# untitled.net
KiCad netlist of a schematic drawn in EAGLE
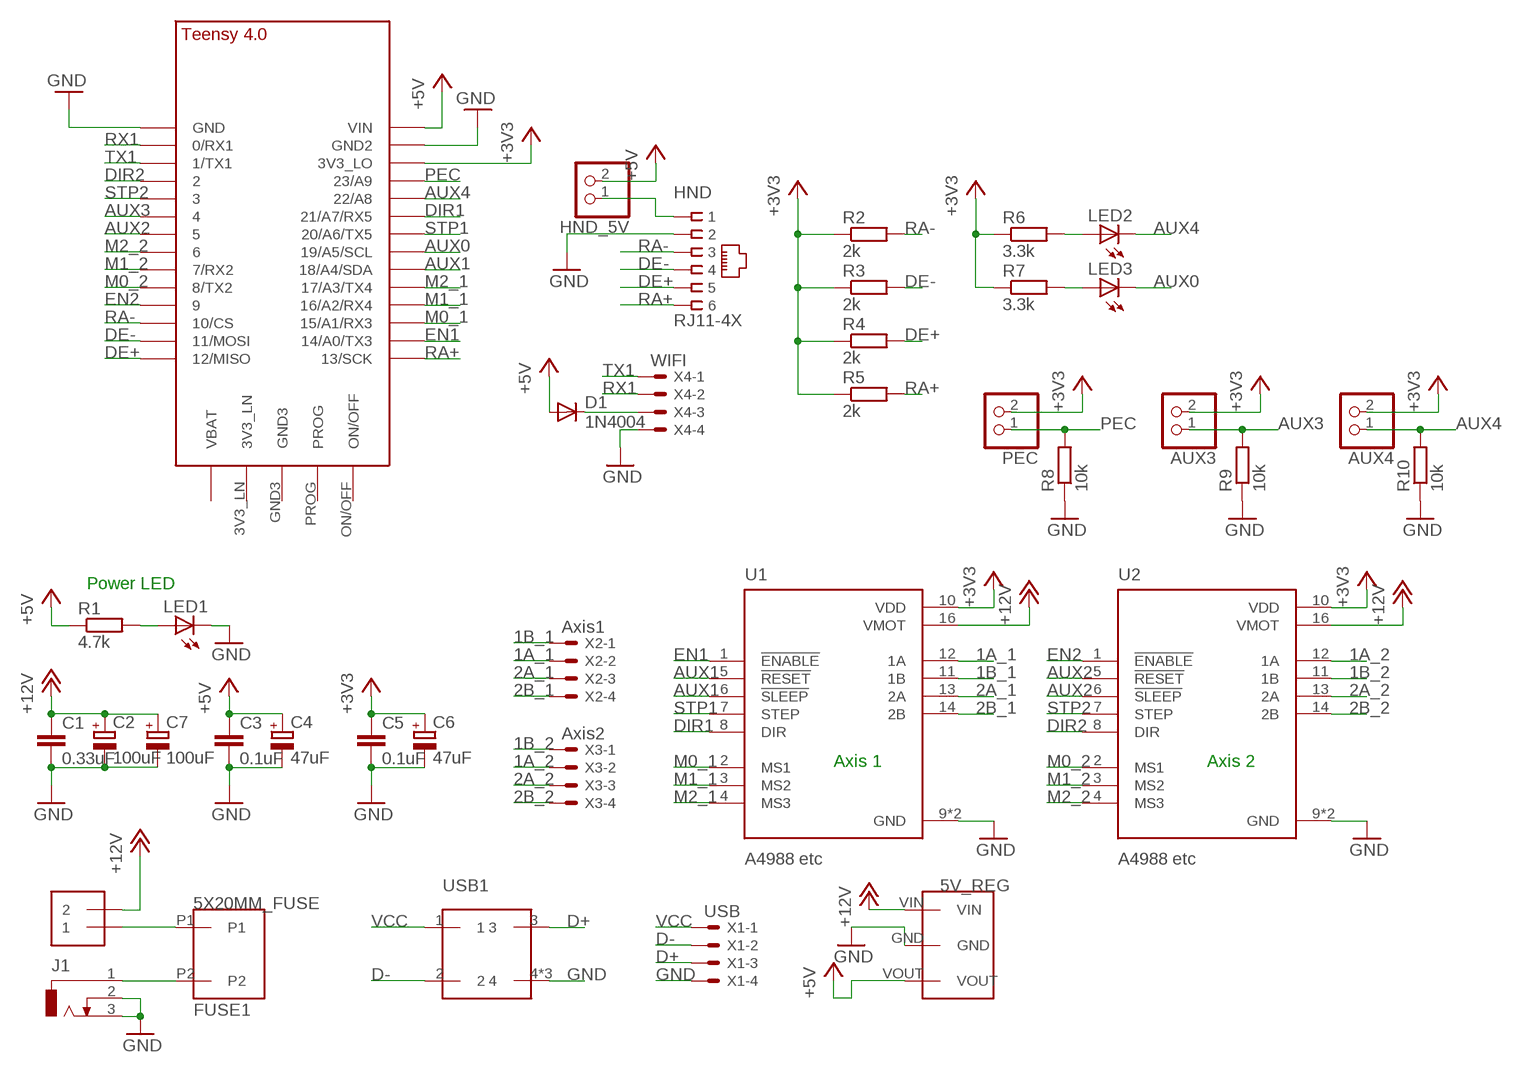
[diagram p0: schematic, sheet 1]

(export (version "E")
  (design (tool "Eeschema 10.0.6"))
  (components
    (comp (ref "5V_REG")
      (value "TSR_5V")
      (footprint "eagle-import:TSR_5V")
      (libsource (lib "eagle-import") (part "TSR_5V"))
    )
    (comp (ref "AUX3")
      (value "PINHD-1X2")
      (footprint "eagle-import:1X02")
      (libsource (lib "eagle-import") (part "PINHD-1X2"))
    )
    (comp (ref "AUX4")
      (value "PINHD-1X2")
      (footprint "eagle-import:1X02")
      (libsource (lib "eagle-import") (part "PINHD-1X2"))
    )
    (comp (ref "C1")
      (value "0.33uF")
      (footprint "eagle-import:C050-024X044")
      (libsource (lib "eagle-import") (part "C-EU050-024X044"))
    )
    (comp (ref "C2")
      (value "100uF")
      (footprint "eagle-import:E5-8,5")
      (libsource (lib "eagle-import") (part "CPOL-EUE5-8.5"))
    )
    (comp (ref "C3")
      (value "0.1uF")
      (footprint "eagle-import:C050-024X044")
      (libsource (lib "eagle-import") (part "C-EU050-024X044"))
    )
    (comp (ref "C4")
      (value "47uF")
      (footprint "eagle-import:E5-8,5")
      (libsource (lib "eagle-import") (part "CPOL-EUE5-8.5"))
    )
    (comp (ref "C5")
      (value "0.1uF")
      (footprint "eagle-import:C050-024X044")
      (libsource (lib "eagle-import") (part "C-EU050-024X044"))
    )
    (comp (ref "C6")
      (value "47uF")
      (footprint "eagle-import:E5-8,5")
      (libsource (lib "eagle-import") (part "CPOL-EUE5-8.5"))
    )
    (comp (ref "C7")
      (value "100uF")
      (footprint "eagle-import:E5-8,5")
      (libsource (lib "eagle-import") (part "CPOL-EUE5-8.5"))
    )
    (comp (ref "D1")
      (value "1N4004")
      (footprint "eagle-import:DO41-10")
      (libsource (lib "eagle-import") (part "1N4004"))
    )
    (comp (ref "FUSE1")
      (value "5X20MM_FUSE")
      (footprint "eagle-import:5X20MM_FUSE")
      (libsource (lib "eagle-import") (part "5X20MM_FUSE"))
    )
    (comp (ref "HND")
      (value "RJ11-4X")
      (footprint "eagle-import:RJ11-NO_SHIELD")
      (fields (field (name "MPN") "6609214-3"))
      (libsource (lib "eagle-import") (part "RJ11-4X"))
    )
    (comp (ref "HND_5V")
      (value "PINHD-1X2")
      (footprint "eagle-import:1X02")
      (libsource (lib "eagle-import") (part "PINHD-1X2"))
    )
    (comp (ref "J1")
      (value "DCJ0303")
      (footprint "eagle-import:DCJ0303")
      (libsource (lib "eagle-import") (part "DCJ0303"))
    )
    (comp (ref "LED1")
      (value "LED5MM")
      (footprint "eagle-import:LED5MM")
      (libsource (lib "eagle-import") (part "LED5MM"))
    )
    (comp (ref "LED2")
      (value "LED5MM")
      (footprint "eagle-import:LED5MM")
      (libsource (lib "eagle-import") (part "LED5MM"))
    )
    (comp (ref "LED3")
      (value "LED5MM")
      (footprint "eagle-import:LED5MM")
      (libsource (lib "eagle-import") (part "LED5MM"))
    )
    (comp (ref "PEC")
      (value "PINHD-1X2")
      (footprint "eagle-import:1X02")
      (libsource (lib "eagle-import") (part "PINHD-1X2"))
    )
    (comp (ref "R1")
      (value "4.7k")
      (footprint "eagle-import:0207_7")
      (libsource (lib "eagle-import") (part "R-EU_0207/7"))
    )
    (comp (ref "R2")
      (value "2k")
      (footprint "eagle-import:0207_7")
      (libsource (lib "eagle-import") (part "R-EU_0207/7"))
    )
    (comp (ref "R3")
      (value "2k")
      (footprint "eagle-import:0207_7")
      (libsource (lib "eagle-import") (part "R-EU_0207/7"))
    )
    (comp (ref "R4")
      (value "2k")
      (footprint "eagle-import:0207_7")
      (libsource (lib "eagle-import") (part "R-EU_0207/7"))
    )
    (comp (ref "R5")
      (value "2k")
      (footprint "eagle-import:0207_7")
      (libsource (lib "eagle-import") (part "R-EU_0207/7"))
    )
    (comp (ref "R6")
      (value "3.3k")
      (footprint "eagle-import:0207_7")
      (libsource (lib "eagle-import") (part "R-EU_0207/7"))
    )
    (comp (ref "R7")
      (value "3.3k")
      (footprint "eagle-import:0207_7")
      (libsource (lib "eagle-import") (part "R-EU_0207/7"))
    )
    (comp (ref "R8")
      (value "10k")
      (footprint "eagle-import:0207_7")
      (libsource (lib "eagle-import") (part "R-EU_0207/7"))
    )
    (comp (ref "R9")
      (value "10k")
      (footprint "eagle-import:0207_7")
      (libsource (lib "eagle-import") (part "R-EU_0207/7"))
    )
    (comp (ref "R10")
      (value "10k")
      (footprint "eagle-import:0207_7")
      (libsource (lib "eagle-import") (part "R-EU_0207/7"))
    )
    (comp (ref "SWITCH")
      (value "1X2-3.5MM")
      (footprint "eagle-import:1X2-3.5MM")
      (libsource (lib "eagle-import") (part "1X2-3.5MM"))
    )
    (comp (ref "U$1")
      (value "TEENSY_4.0")
      (footprint "eagle-import:TEENSY_4.0")
      (libsource (lib "eagle-import") (part "TEENSY_4.0"))
    )
    (comp (ref "U1")
      (value "A4988 etc")
      (footprint "eagle-import:MODULE_A4988_STEPPER_MOTOR_DRIVER_CARRIER")
      (fields (field (name "MF") "Pololu") (field (name "MP") "A4988 STEPPER MOTOR DRIVER CARRIER"))
      (libsource (lib "eagle-import") (part "A4988_STEPPER_MOTOR_DRIVER_CARRIER"))
    )
    (comp (ref "U2")
      (value "A4988 etc")
      (footprint "eagle-import:MODULE_A4988_STEPPER_MOTOR_DRIVER_CARRIER")
      (fields (field (name "MF") "Pololu") (field (name "MP") "A4988 STEPPER MOTOR DRIVER CARRIER"))
      (libsource (lib "eagle-import") (part "A4988_STEPPER_MOTOR_DRIVER_CARRIER"))
    )
    (comp (ref "USB1")
      (value "USB-B_SOCKET")
      (footprint "eagle-import:USB-B_SOCKET")
      (libsource (lib "eagle-import") (part "USB-B_SOCKET"))
    )
    (comp (ref "X1")
      (value "USB")
      (footprint "eagle-import:JST-XH-04-PACKAGE-ROUND-PAD")
      (libsource (lib "eagle-import") (part "JST-XH-04-PIN-ROUND-PAD"))
    )
    (comp (ref "X2")
      (value "Axis1")
      (footprint "eagle-import:JST-XH-04-PACKAGE-LONG-PAD")
      (libsource (lib "eagle-import") (part "JST-XH-04-PIN-LONG-PAD"))
    )
    (comp (ref "X3")
      (value "Axis2")
      (footprint "eagle-import:JST-XH-04-PACKAGE-LONG-PAD")
      (libsource (lib "eagle-import") (part "JST-XH-04-PIN-LONG-PAD"))
    )
    (comp (ref "X4")
      (value "WIFI")
      (footprint "eagle-import:JST-XH-04-PACKAGE-LONG-PAD")
      (libsource (lib "eagle-import") (part "JST-XH-04-PIN-LONG-PAD"))
    )
  )
  (nets
    (net (code "1") (name "+3V3") (class "Default")
      (node (ref "AUX3") (pin "2") (pinfunction "2_2") (pintype "passive"))
      (node (ref "AUX4") (pin "2") (pinfunction "2_2") (pintype "passive"))
      (node (ref "C5") (pin "1") (pinfunction "1_1") (pintype "passive"))
      (node (ref "C6") (pin "+") (pinfunction "+_+") (pintype "passive"))
      (node (ref "PEC") (pin "2") (pinfunction "2_2") (pintype "passive"))
      (node (ref "R2") (pin "1") (pinfunction "1_1") (pintype "passive"))
      (node (ref "R3") (pin "1") (pinfunction "1_1") (pintype "passive"))
      (node (ref "R4") (pin "1") (pinfunction "1_1") (pintype "passive"))
      (node (ref "R5") (pin "1") (pinfunction "1_1") (pintype "passive"))
      (node (ref "R6") (pin "1") (pinfunction "1_1") (pintype "passive"))
      (node (ref "R7") (pin "1") (pinfunction "1_1") (pintype "passive"))
      (node (ref "U$1") (pin "3V3_LO") (pinfunction "3V3_LO_3V3_LO") (pintype "bidirectional"))
      (node (ref "U1") (pin "10") (pinfunction "VDD_10") (pintype "power_in"))
      (node (ref "U2") (pin "10") (pinfunction "VDD_10") (pintype "power_in"))
    )
    (net (code "2") (name "+5V") (class "Default")
      (node (ref "5V_REG") (pin "VOUT") (pinfunction "VOUT_VOUT") (pintype "bidirectional"))
      (node (ref "C3") (pin "1") (pinfunction "1_1") (pintype "passive"))
      (node (ref "C4") (pin "+") (pinfunction "+_+") (pintype "passive"))
      (node (ref "D1") (pin "A") (pinfunction "A_A") (pintype "passive"))
      (node (ref "HND_5V") (pin "2") (pinfunction "2_2") (pintype "passive"))
      (node (ref "R1") (pin "1") (pinfunction "1_1") (pintype "passive"))
      (node (ref "U$1") (pin "VIN") (pinfunction "VIN_VIN") (pintype "bidirectional"))
    )
    (net (code "3") (name "+12V") (class "Default")
      (node (ref "5V_REG") (pin "VIN") (pinfunction "VIN_VIN") (pintype "bidirectional"))
      (node (ref "C1") (pin "1") (pinfunction "1_1") (pintype "passive"))
      (node (ref "C2") (pin "+") (pinfunction "+_+") (pintype "passive"))
      (node (ref "C7") (pin "+") (pinfunction "+_+") (pintype "passive"))
      (node (ref "SWITCH") (pin "2") (pinfunction "2_2") (pintype "passive"))
      (node (ref "U1") (pin "16") (pinfunction "VMOT_16") (pintype "power_in"))
      (node (ref "U2") (pin "16") (pinfunction "VMOT_16") (pintype "power_in"))
    )
    (net (code "4") (name "/1A_1") (class "Default")
      (node (ref "U1") (pin "12") (pinfunction "1A_12") (pintype "output"))
      (node (ref "X2") (pin "2") (pinfunction "S_2") (pintype "passive"))
    )
    (net (code "5") (name "/1A_2") (class "Default")
      (node (ref "U2") (pin "12") (pinfunction "1A_12") (pintype "output"))
      (node (ref "X3") (pin "2") (pinfunction "S_2") (pintype "passive"))
    )
    (net (code "6") (name "/1B_1") (class "Default")
      (node (ref "U1") (pin "11") (pinfunction "1B_11") (pintype "output"))
      (node (ref "X2") (pin "1") (pinfunction "S_1") (pintype "passive"))
    )
    (net (code "7") (name "/1B_2") (class "Default")
      (node (ref "U2") (pin "11") (pinfunction "1B_11") (pintype "output"))
      (node (ref "X3") (pin "1") (pinfunction "S_1") (pintype "passive"))
    )
    (net (code "8") (name "/2A_1") (class "Default")
      (node (ref "U1") (pin "13") (pinfunction "2A_13") (pintype "output"))
      (node (ref "X2") (pin "3") (pinfunction "S_3") (pintype "passive"))
    )
    (net (code "9") (name "/2A_2") (class "Default")
      (node (ref "U2") (pin "13") (pinfunction "2A_13") (pintype "output"))
      (node (ref "X3") (pin "3") (pinfunction "S_3") (pintype "passive"))
    )
    (net (code "10") (name "/2B_1") (class "Default")
      (node (ref "U1") (pin "14") (pinfunction "2B_14") (pintype "output"))
      (node (ref "X2") (pin "4") (pinfunction "S_4") (pintype "passive"))
    )
    (net (code "11") (name "/2B_2") (class "Default")
      (node (ref "U2") (pin "14") (pinfunction "2B_14") (pintype "output"))
      (node (ref "X3") (pin "4") (pinfunction "S_4") (pintype "passive"))
    )
    (net (code "12") (name "/AUX0") (class "Default")
      (node (ref "LED3") (pin "K") (pinfunction "C_K") (pintype "passive"))
      (node (ref "U$1") (pin "19/A5/SCL") (pinfunction "19/A5/SCL_19/A5/SCL") (pintype "bidirectional"))
    )
    (net (code "13") (name "/AUX1") (class "Default")
      (node (ref "U$1") (pin "18/A4/SDA") (pinfunction "18/A4/SDA_18/A4/SDA") (pintype "bidirectional"))
      (node (ref "U1") (pin "5") (pinfunction "~{RESET}_5") (pintype "input"))
      (node (ref "U1") (pin "6") (pinfunction "~{SLEEP}_6") (pintype "input"))
    )
    (net (code "14") (name "/AUX2") (class "Default")
      (node (ref "U$1") (pin "5") (pinfunction "5_5") (pintype "bidirectional"))
      (node (ref "U2") (pin "5") (pinfunction "~{RESET}_5") (pintype "input"))
      (node (ref "U2") (pin "6") (pinfunction "~{SLEEP}_6") (pintype "input"))
    )
    (net (code "15") (name "/AUX3") (class "Default")
      (node (ref "AUX3") (pin "1") (pinfunction "1_1") (pintype "passive"))
      (node (ref "R9") (pin "2") (pinfunction "2_2") (pintype "passive"))
      (node (ref "U$1") (pin "4/CANRX") (pinfunction "4_4/CANRX") (pintype "bidirectional"))
    )
    (net (code "16") (name "/AUX4") (class "Default")
      (node (ref "AUX4") (pin "1") (pinfunction "1_1") (pintype "passive"))
      (node (ref "LED2") (pin "K") (pinfunction "C_K") (pintype "passive"))
      (node (ref "R10") (pin "2") (pinfunction "2_2") (pintype "passive"))
      (node (ref "U$1") (pin "22/A8") (pinfunction "22/A8_22/A8") (pintype "bidirectional"))
    )
    (net (code "17") (name "/D+") (class "Default")
      (node (ref "USB1") (pin "3") (pinfunction "3_3") (pintype "bidirectional"))
      (node (ref "X1") (pin "3") (pinfunction "S_3") (pintype "passive"))
    )
    (net (code "18") (name "/D-") (class "Default")
      (node (ref "USB1") (pin "2") (pinfunction "2_2") (pintype "bidirectional"))
      (node (ref "X1") (pin "2") (pinfunction "S_2") (pintype "passive"))
    )
    (net (code "19") (name "/DE+") (class "Default")
      (node (ref "HND") (pin "5") (pinfunction "5_5") (pintype "passive"))
      (node (ref "R4") (pin "2") (pinfunction "2_2") (pintype "passive"))
      (node (ref "U$1") (pin "12/MISO") (pinfunction "12/MISO_12/MISO") (pintype "bidirectional"))
    )
    (net (code "20") (name "/DE-") (class "Default")
      (node (ref "HND") (pin "4") (pinfunction "4_4") (pintype "passive"))
      (node (ref "R3") (pin "2") (pinfunction "2_2") (pintype "passive"))
      (node (ref "U$1") (pin "11/MOSI") (pinfunction "11/MOSI_11/MOSI") (pintype "bidirectional"))
    )
    (net (code "21") (name "/DIR1") (class "Default")
      (node (ref "U$1") (pin "21/A7") (pinfunction "21/A7/RX5_21/A7") (pintype "bidirectional"))
      (node (ref "U1") (pin "8") (pinfunction "DIR_8") (pintype "input"))
    )
    (net (code "22") (name "/DIR2") (class "Default")
      (node (ref "U$1") (pin "2") (pinfunction "2_2") (pintype "bidirectional"))
      (node (ref "U2") (pin "8") (pinfunction "DIR_8") (pintype "input"))
    )
    (net (code "23") (name "/EN1") (class "Default")
      (node (ref "U$1") (pin "14/A0") (pinfunction "14/A0/TX3_14/A0") (pintype "bidirectional"))
      (node (ref "U1") (pin "1") (pinfunction "~{ENABLE}_1") (pintype "input"))
    )
    (net (code "24") (name "/EN2") (class "Default")
      (node (ref "U$1") (pin "9/CS") (pinfunction "9_9/CS") (pintype "bidirectional"))
      (node (ref "U2") (pin "1") (pinfunction "~{ENABLE}_1") (pintype "input"))
    )
    (net (code "25") (name "/M0_1") (class "Default")
      (node (ref "U$1") (pin "15/A1") (pinfunction "15/A1/RX3_15/A1") (pintype "bidirectional"))
      (node (ref "U1") (pin "2") (pinfunction "MS1_2") (pintype "input"))
    )
    (net (code "26") (name "/M0_2") (class "Default")
      (node (ref "U$1") (pin "8") (pinfunction "8/TX2_8") (pintype "bidirectional"))
      (node (ref "U2") (pin "2") (pinfunction "MS1_2") (pintype "input"))
    )
    (net (code "27") (name "/M1_1") (class "Default")
      (node (ref "U$1") (pin "16/A2") (pinfunction "16/A2/RX4_16/A2") (pintype "bidirectional"))
      (node (ref "U1") (pin "3") (pinfunction "MS2_3") (pintype "input"))
    )
    (net (code "28") (name "/M1_2") (class "Default")
      (node (ref "U$1") (pin "7") (pinfunction "7/RX2_7") (pintype "bidirectional"))
      (node (ref "U2") (pin "3") (pinfunction "MS2_3") (pintype "input"))
    )
    (net (code "29") (name "/M2_1") (class "Default")
      (node (ref "U$1") (pin "17/A3") (pinfunction "17/A3/TX4_17/A3") (pintype "bidirectional"))
      (node (ref "U1") (pin "4") (pinfunction "MS3_4") (pintype "input"))
    )
    (net (code "30") (name "/M2_2") (class "Default")
      (node (ref "U$1") (pin "6") (pinfunction "6_6") (pintype "bidirectional"))
      (node (ref "U2") (pin "4") (pinfunction "MS3_4") (pintype "input"))
    )
    (net (code "31") (name "/PEC") (class "Default")
      (node (ref "PEC") (pin "1") (pinfunction "1_1") (pintype "passive"))
      (node (ref "R8") (pin "2") (pinfunction "2_2") (pintype "passive"))
      (node (ref "U$1") (pin "23/A9") (pinfunction "23/A9_23/A9") (pintype "bidirectional"))
    )
    (net (code "32") (name "/RA+") (class "Default")
      (node (ref "HND") (pin "6") (pinfunction "6_6") (pintype "passive"))
      (node (ref "R5") (pin "2") (pinfunction "2_2") (pintype "passive"))
      (node (ref "U$1") (pin "13/SCK") (pinfunction "13/SCK_13/SCK") (pintype "bidirectional"))
    )
    (net (code "33") (name "/RA-") (class "Default")
      (node (ref "HND") (pin "3") (pinfunction "3_3") (pintype "passive"))
      (node (ref "R2") (pin "2") (pinfunction "2_2") (pintype "passive"))
      (node (ref "U$1") (pin "10/CS") (pinfunction "10/CS_10/CS") (pintype "bidirectional"))
    )
    (net (code "34") (name "/RX1") (class "Default")
      (node (ref "U$1") (pin "0/RX") (pinfunction "0/RX1_0/RX") (pintype "bidirectional"))
      (node (ref "X4") (pin "2") (pinfunction "S_2") (pintype "passive"))
    )
    (net (code "35") (name "/STP1") (class "Default")
      (node (ref "U$1") (pin "20/A6") (pinfunction "20/A6/TX5_20/A6") (pintype "bidirectional"))
      (node (ref "U1") (pin "7") (pinfunction "STEP_7") (pintype "input"))
    )
    (net (code "36") (name "/STP2") (class "Default")
      (node (ref "U$1") (pin "3/CANTX") (pinfunction "3_3/CANTX") (pintype "bidirectional"))
      (node (ref "U2") (pin "7") (pinfunction "STEP_7") (pintype "input"))
    )
    (net (code "37") (name "/TX1") (class "Default")
      (node (ref "U$1") (pin "1/TX") (pinfunction "1/TX1_1/TX") (pintype "bidirectional"))
      (node (ref "X4") (pin "1") (pinfunction "S_1") (pintype "passive"))
    )
    (net (code "38") (name "/VCC") (class "Default")
      (node (ref "USB1") (pin "1") (pinfunction "1_1") (pintype "bidirectional"))
      (node (ref "X1") (pin "1") (pinfunction "S_1") (pintype "passive"))
    )
    (net (code "39") (name "GND") (class "Default")
      (node (ref "5V_REG") (pin "GND") (pinfunction "GND_GND") (pintype "bidirectional"))
      (node (ref "C1") (pin "2") (pinfunction "2_2") (pintype "passive"))
      (node (ref "C2") (pin "-") (pinfunction "-_-") (pintype "passive"))
      (node (ref "C3") (pin "2") (pinfunction "2_2") (pintype "passive"))
      (node (ref "C4") (pin "-") (pinfunction "-_-") (pintype "passive"))
      (node (ref "C5") (pin "2") (pinfunction "2_2") (pintype "passive"))
      (node (ref "C6") (pin "-") (pinfunction "-_-") (pintype "passive"))
      (node (ref "C7") (pin "-") (pinfunction "-_-") (pintype "passive"))
      (node (ref "HND") (pin "2") (pinfunction "2_2") (pintype "passive"))
      (node (ref "J1") (pin "2") (pinfunction "2_2") (pintype "passive"))
      (node (ref "J1") (pin "3") (pinfunction "3_3") (pintype "passive"))
      (node (ref "LED1") (pin "K") (pinfunction "C_K") (pintype "passive"))
      (node (ref "R10") (pin "1") (pinfunction "1_1") (pintype "passive"))
      (node (ref "R8") (pin "1") (pinfunction "1_1") (pintype "passive"))
      (node (ref "R9") (pin "1") (pinfunction "1_1") (pintype "passive"))
      (node (ref "U$1") (pin "GND") (pinfunction "GND_GND") (pintype "bidirectional"))
      (node (ref "U$1") (pin "GND2") (pinfunction "GND2_GND2") (pintype "bidirectional"))
      (node (ref "U1") (pin "15") (pinfunction "GND_15") (pintype "power_in"))
      (node (ref "U1") (pin "9") (pinfunction "GND_9") (pintype "power_in"))
      (node (ref "U2") (pin "15") (pinfunction "GND_15") (pintype "power_in"))
      (node (ref "U2") (pin "9") (pinfunction "GND_9") (pintype "power_in"))
      (node (ref "USB1") (pin "4") (pinfunction "4_4") (pintype "bidirectional"))
      (node (ref "USB1") (pin "P$1") (pinfunction "4_P$1") (pintype "bidirectional"))
      (node (ref "USB1") (pin "P$2") (pinfunction "4_P$2") (pintype "bidirectional"))
      (node (ref "X1") (pin "4") (pinfunction "S_4") (pintype "passive"))
      (node (ref "X4") (pin "4") (pinfunction "S_4") (pintype "passive"))
    )
    (net (code "40") (name "Net-(FUSE1-PadP1)") (class "Default")
      (node (ref "FUSE1") (pin "P1") (pinfunction "P1_P1") (pintype "bidirectional"))
      (node (ref "SWITCH") (pin "1") (pinfunction "1_1") (pintype "passive"))
    )
    (net (code "41") (name "Net-(FUSE1-PadP2)") (class "Default")
      (node (ref "FUSE1") (pin "P2") (pinfunction "P2_P2") (pintype "bidirectional"))
      (node (ref "J1") (pin "1") (pinfunction "1_1") (pintype "passive"))
    )
    (net (code "42") (name "Net-(HND-Pad1)") (class "Default")
      (node (ref "HND") (pin "1") (pinfunction "1_1") (pintype "passive"))
      (node (ref "HND_5V") (pin "1") (pinfunction "1_1") (pintype "passive"))
    )
    (net (code "43") (name "Net-(LED1-PadA)") (class "Default")
      (node (ref "LED1") (pin "A") (pinfunction "A_A") (pintype "passive"))
      (node (ref "R1") (pin "2") (pinfunction "2_2") (pintype "passive"))
    )
    (net (code "44") (name "Net-(LED2-PadA)") (class "Default")
      (node (ref "LED2") (pin "A") (pinfunction "A_A") (pintype "passive"))
      (node (ref "R6") (pin "2") (pinfunction "2_2") (pintype "passive"))
    )
    (net (code "45") (name "Net-(LED3-PadA)") (class "Default")
      (node (ref "LED3") (pin "A") (pinfunction "A_A") (pintype "passive"))
      (node (ref "R7") (pin "2") (pinfunction "2_2") (pintype "passive"))
    )
    (net (code "46") (name "Net-(X4C-S)") (class "Default")
      (node (ref "D1") (pin "C") (pinfunction "C_C") (pintype "passive"))
      (node (ref "X4") (pin "3") (pinfunction "S_3") (pintype "passive"))
    )
    (net (code "47") (name "unconnected-(U$1-Pad3V3_LN)") (class "Default")
      (node (ref "U$1") (pin "3V3_LN") (pinfunction "3V3_LN_3V3_LN") (pintype "bidirectional"))
    )
    (net (code "48") (name "unconnected-(U$1-PadGND3)") (class "Default")
      (node (ref "U$1") (pin "GND3") (pinfunction "GND3_GND3") (pintype "bidirectional"))
    )
    (net (code "49") (name "unconnected-(U$1-PadON{slash}OFF)") (class "Default")
      (node (ref "U$1") (pin "ON/OFF") (pinfunction "ON/OFF_ON/OFF") (pintype "bidirectional"))
    )
    (net (code "50") (name "unconnected-(U$1-PadPROG)") (class "Default")
      (node (ref "U$1") (pin "PROG") (pinfunction "PROG_PROG") (pintype "bidirectional"))
    )
    (net (code "51") (name "unconnected-(U$1-VBAT-PadVBAT\\)") (class "Default")
      (node (ref "U$1") (pin "VBAT\\") (pinfunction "VBAT_VBAT\\") (pintype "bidirectional"))
    )
  )
)
